# sheet3_memory.net
KiCad netlist of a schematic drawn in Altium Designer
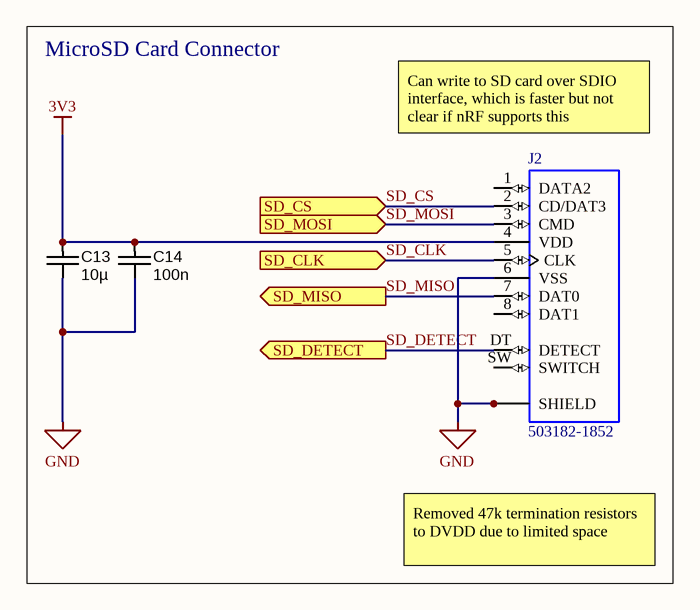
[diagram p0: sheet3_memory.SchDoc]

(export (version "E")
  (design (tool "Eeschema 10.0.6"))
  (components
    (comp (ref "C13")
      (value "10µ")
      (footprint "CAPC2012X135N")
      (description "Capacitor SMD Cer 10uF 10% 10V X5R 0805")
      (fields (field (name "TOLERANCE") "±10%") (field (name "Comment") "approved sub OK"))
      (libsource (lib "Libs_RRutledge") (part "CAPC_10u_0805_10V"))
    )
    (comp (ref "C14")
      (value "100n")
      (footprint "CAPC1005X55N")
      (description "Capacitor SMD Cer 100nF 10% 16V X5R 0402")
      (fields (field (name "TOLERANCE") "±10%"))
      (libsource (lib "Libs_RRutledge") (part "CAPC_100n_0402_X5R_16V_10%"))
    )
    (comp (ref "J2")
      (value "503182-1852")
      (footprint "MOLEX_503182-1852")
      (description "10 _8 + 2_ Position Card Connector microSDâ„¢ Surface Mount, Right Angle Gold")
      (fields (field (name "MF") "Molex") (field (name "DIGI-KEY_PART_NUMBER") "WM12834CT-ND"))
      (libsource (lib "503182-1852") (part "503182-1852"))
    )
  )
  (nets
    (net (code "1") (name "/SD_CLK") (class "Default")
      (node (ref "J2") (pin "5") (pinfunction "CLK_5") (pintype "bidirectional"))
    )
    (net (code "2") (name "/SD_CS") (class "Default")
      (node (ref "J2") (pin "2") (pinfunction "CD/DAT3_2") (pintype "bidirectional"))
    )
    (net (code "3") (name "/SD_DETECT") (class "Default")
      (node (ref "J2") (pin "DT") (pinfunction "DETECT_DT") (pintype "bidirectional"))
    )
    (net (code "4") (name "/SD_MISO") (class "Default")
      (node (ref "J2") (pin "7") (pinfunction "DAT0_7") (pintype "bidirectional"))
    )
    (net (code "5") (name "/SD_MOSI") (class "Default")
      (node (ref "J2") (pin "3") (pinfunction "CMD_3") (pintype "bidirectional"))
    )
    (net (code "6") (name "3V3") (class "Default")
      (node (ref "C13") (pin "1") (pintype "passive"))
      (node (ref "C14") (pin "1") (pintype "passive"))
      (node (ref "J2") (pin "4") (pinfunction "VDD_4") (pintype "power_in"))
    )
    (net (code "7") (name "GND") (class "Default")
      (node (ref "C13") (pin "2") (pintype "passive"))
      (node (ref "C14") (pin "2") (pintype "passive"))
      (node (ref "J2") (pin "6") (pinfunction "VSS_6") (pintype "power_in"))
      (node (ref "J2") (pin "P1") (pinfunction "SHIELD_P1") (pintype "passive"))
      (node (ref "J2") (pin "P2") (pinfunction "SHIELD_P2") (pintype "passive"))
      (node (ref "J2") (pin "P3") (pinfunction "SHIELD_P3") (pintype "passive"))
      (node (ref "J2") (pin "P4") (pinfunction "SHIELD_P4") (pintype "passive"))
      (node (ref "J2") (pin "P5") (pinfunction "SHIELD_P5") (pintype "passive"))
    )
    (net (code "8") (name "unconnected-(J2-DAT1-Pad8)") (class "Default")
      (node (ref "J2") (pin "8") (pinfunction "DAT1_8") (pintype "bidirectional"))
    )
    (net (code "9") (name "unconnected-(J2-DATA2-Pad1)") (class "Default")
      (node (ref "J2") (pin "1") (pinfunction "DATA2_1") (pintype "bidirectional"))
    )
    (net (code "10") (name "unconnected-(J2-SWITCH-PadSW)") (class "Default")
      (node (ref "J2") (pin "SW") (pinfunction "SWITCH_SW") (pintype "bidirectional"))
    )
  )
)
